# MotorDriver.net
KiCad netlist of a schematic drawn in EAGLE
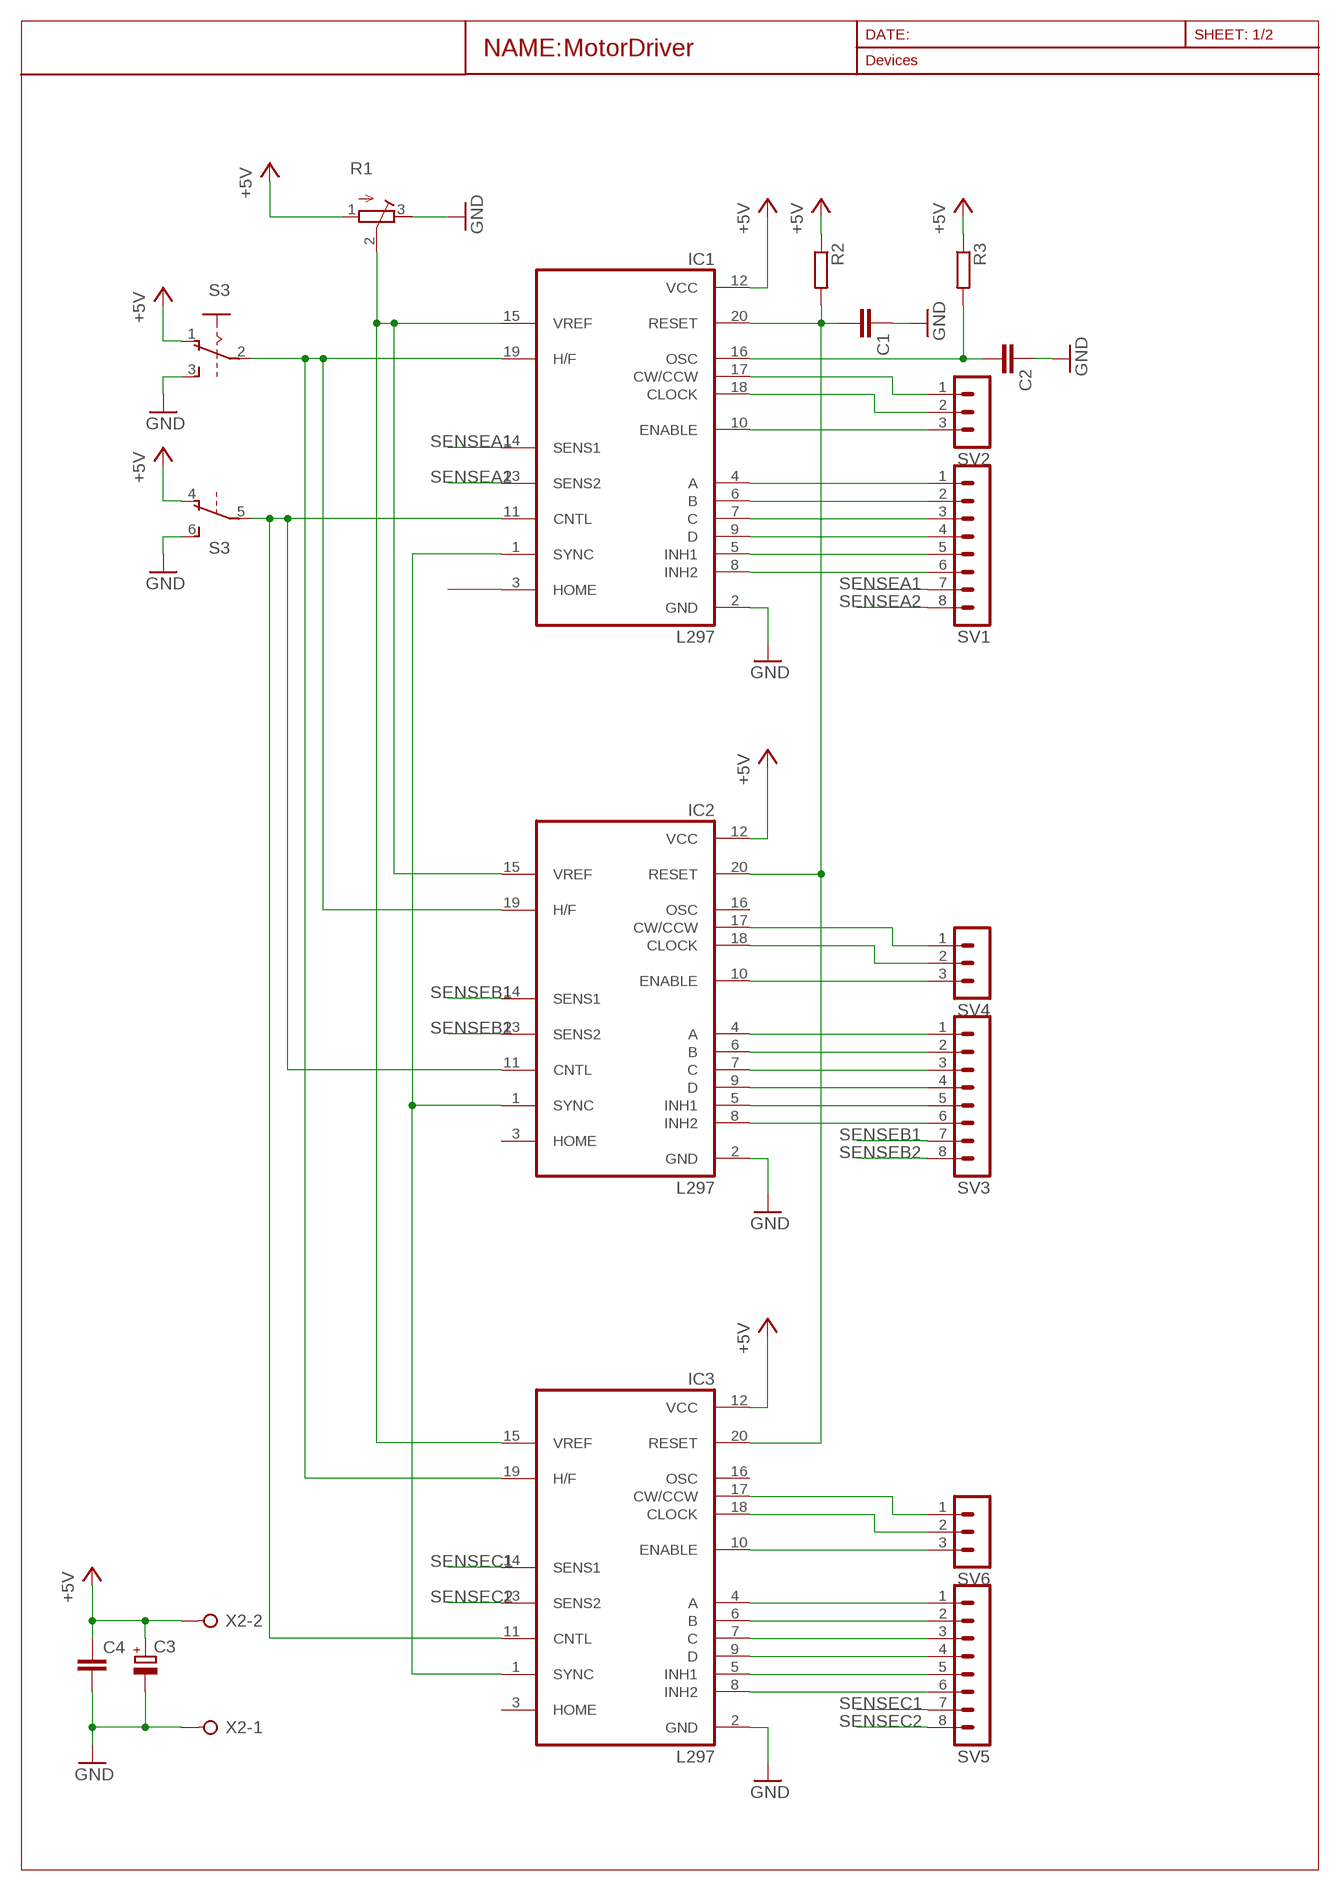
[diagram p0: schematic, sheet 1]

(export (version "E")
  (design (tool "Eeschema 10.0.6"))
  (components
    (comp (ref "C1")
      (value "C-EU050-024X044")
      (footprint "eagle-import:C050-024X044")
      (libsource (lib "eagle-import") (part "C-EU050-024X044"))
    )
    (comp (ref "C2")
      (value "C-EU050-024X044")
      (footprint "eagle-import:C050-024X044")
      (libsource (lib "eagle-import") (part "C-EU050-024X044"))
    )
    (comp (ref "C3")
      (value "CPOL-EUE3.5-8")
      (footprint "eagle-import:E3,5-8")
      (libsource (lib "eagle-import") (part "CPOL-EUE3.5-8"))
    )
    (comp (ref "C4")
      (value "C-EU050-024X044")
      (footprint "eagle-import:C050-024X044")
      (libsource (lib "eagle-import") (part "C-EU050-024X044"))
    )
    (comp (ref "IC1")
      (value "L297")
      (footprint "eagle-import:DIL20")
      (fields (field (name "MPN") "L297/1"))
      (libsource (lib "eagle-import") (part "L297"))
    )
    (comp (ref "IC2")
      (value "L297")
      (footprint "eagle-import:DIL20")
      (fields (field (name "MPN") "L297/1"))
      (libsource (lib "eagle-import") (part "L297"))
    )
    (comp (ref "IC3")
      (value "L297")
      (footprint "eagle-import:DIL20")
      (fields (field (name "MPN") "L297/1"))
      (libsource (lib "eagle-import") (part "L297"))
    )
    (comp (ref "R1")
      (value "R-TRIMM64P")
      (footprint "eagle-import:RTRIM64P")
      (libsource (lib "eagle-import") (part "R-TRIMM64P"))
    )
    (comp (ref "R2")
      (value "R-EU_0207/10")
      (footprint "eagle-import:0207_10")
      (libsource (lib "eagle-import") (part "R-EU_0207/10"))
    )
    (comp (ref "R3")
      (value "R-EU_0207/10")
      (footprint "eagle-import:0207_10")
      (libsource (lib "eagle-import") (part "R-EU_0207/10"))
    )
    (comp (ref "S3")
      (value "A68-A31")
      (footprint "eagle-import:A68-A31")
      (libsource (lib "eagle-import") (part "A68-A31"))
    )
    (comp (ref "SV1")
      (value "MA08-1")
      (footprint "eagle-import:MA08-1")
      (libsource (lib "eagle-import") (part "MA08-1"))
    )
    (comp (ref "SV2")
      (value "MA03-1")
      (footprint "eagle-import:MA03-1")
      (libsource (lib "eagle-import") (part "MA03-1"))
    )
    (comp (ref "SV3")
      (value "MA08-1")
      (footprint "eagle-import:MA08-1")
      (libsource (lib "eagle-import") (part "MA08-1"))
    )
    (comp (ref "SV4")
      (value "MA03-1")
      (footprint "eagle-import:MA03-1")
      (libsource (lib "eagle-import") (part "MA03-1"))
    )
    (comp (ref "SV5")
      (value "MA08-1")
      (footprint "eagle-import:MA08-1")
      (libsource (lib "eagle-import") (part "MA08-1"))
    )
    (comp (ref "SV6")
      (value "MA03-1")
      (footprint "eagle-import:MA03-1")
      (libsource (lib "eagle-import") (part "MA03-1"))
    )
    (comp (ref "X2")
      (value "W237-02P")
      (footprint "eagle-import:W237-132")
      (libsource (lib "eagle-import") (part "W237-02P"))
    )
  )
  (nets
    (net (code "1") (name "+5V") (class "Default")
      (node (ref "C3") (pin "+") (pinfunction "+_+") (pintype "passive"))
      (node (ref "C4") (pin "1") (pinfunction "1_1") (pintype "passive"))
      (node (ref "IC1") (pin "12") (pinfunction "VCC_12") (pintype "power_in"))
      (node (ref "IC2") (pin "12") (pinfunction "VCC_12") (pintype "power_in"))
      (node (ref "IC3") (pin "12") (pinfunction "VCC_12") (pintype "power_in"))
      (node (ref "R1") (pin "1") (pinfunction "A_1") (pintype "passive"))
      (node (ref "R2") (pin "1") (pinfunction "1_1") (pintype "passive"))
      (node (ref "R3") (pin "1") (pinfunction "1_1") (pintype "passive"))
      (node (ref "S3") (pin "1") (pinfunction "O_1") (pintype "passive"))
      (node (ref "S3") (pin "4") (pinfunction "O_4") (pintype "passive"))
      (node (ref "X2") (pin "2") (pinfunction "KL_2") (pintype "passive"))
    )
    (net (code "2") (name "GND") (class "Default")
      (node (ref "C1") (pin "1") (pinfunction "1_1") (pintype "passive"))
      (node (ref "C2") (pin "1") (pinfunction "1_1") (pintype "passive"))
      (node (ref "C3") (pin "-") (pinfunction "-_-") (pintype "passive"))
      (node (ref "C4") (pin "2") (pinfunction "2_2") (pintype "passive"))
      (node (ref "IC1") (pin "2") (pinfunction "GND_2") (pintype "power_in"))
      (node (ref "IC2") (pin "2") (pinfunction "GND_2") (pintype "power_in"))
      (node (ref "IC3") (pin "2") (pinfunction "GND_2") (pintype "power_in"))
      (node (ref "R1") (pin "3") (pinfunction "E_3") (pintype "passive"))
      (node (ref "S3") (pin "3") (pinfunction "S_3") (pintype "passive"))
      (node (ref "S3") (pin "6") (pinfunction "S_6") (pintype "passive"))
      (node (ref "X2") (pin "1") (pinfunction "KL_1") (pintype "passive"))
    )
    (net (code "3") (name "Net-(IC1-A)") (class "Default")
      (node (ref "IC1") (pin "4") (pinfunction "A_4") (pintype "output"))
      (node (ref "SV1") (pin "1") (pinfunction "1_1") (pintype "passive"))
    )
    (net (code "4") (name "Net-(IC1-B)") (class "Default")
      (node (ref "IC1") (pin "6") (pinfunction "B_6") (pintype "output"))
      (node (ref "SV1") (pin "2") (pinfunction "2_2") (pintype "passive"))
    )
    (net (code "5") (name "Net-(IC1-C)") (class "Default")
      (node (ref "IC1") (pin "7") (pinfunction "C_7") (pintype "output"))
      (node (ref "SV1") (pin "3") (pinfunction "3_3") (pintype "passive"))
    )
    (net (code "6") (name "Net-(IC1-CLOCK)") (class "Default")
      (node (ref "IC1") (pin "18") (pinfunction "CLOCK_18") (pintype "input"))
      (node (ref "SV2") (pin "2") (pinfunction "2_2") (pintype "passive"))
    )
    (net (code "7") (name "Net-(IC1-CNTL)") (class "Default")
      (node (ref "IC1") (pin "11") (pinfunction "CNTL_11") (pintype "input"))
      (node (ref "IC2") (pin "11") (pinfunction "CNTL_11") (pintype "input"))
      (node (ref "IC3") (pin "11") (pinfunction "CNTL_11") (pintype "input"))
      (node (ref "S3") (pin "5") (pinfunction "P_5") (pintype "passive"))
    )
    (net (code "8") (name "Net-(IC1-CW{slash}CCW)") (class "Default")
      (node (ref "IC1") (pin "17") (pinfunction "CW/CCW_17") (pintype "input"))
      (node (ref "SV2") (pin "1") (pinfunction "1_1") (pintype "passive"))
    )
    (net (code "9") (name "Net-(IC1-D)") (class "Default")
      (node (ref "IC1") (pin "9") (pinfunction "D_9") (pintype "output"))
      (node (ref "SV1") (pin "4") (pinfunction "4_4") (pintype "passive"))
    )
    (net (code "10") (name "Net-(IC1-ENABLE)") (class "Default")
      (node (ref "IC1") (pin "10") (pinfunction "ENABLE_10") (pintype "input"))
      (node (ref "SV2") (pin "3") (pinfunction "3_3") (pintype "passive"))
    )
    (net (code "11") (name "Net-(IC1-H{slash}F)") (class "Default")
      (node (ref "IC1") (pin "19") (pinfunction "H/F_19") (pintype "input"))
      (node (ref "IC2") (pin "19") (pinfunction "H/F_19") (pintype "input"))
      (node (ref "IC3") (pin "19") (pinfunction "H/F_19") (pintype "input"))
      (node (ref "S3") (pin "2") (pinfunction "P_2") (pintype "passive"))
    )
    (net (code "12") (name "Net-(IC1-INH1)") (class "Default")
      (node (ref "IC1") (pin "5") (pinfunction "INH1_5") (pintype "output"))
      (node (ref "SV1") (pin "5") (pinfunction "5_5") (pintype "passive"))
    )
    (net (code "13") (name "Net-(IC1-INH2)") (class "Default")
      (node (ref "IC1") (pin "8") (pinfunction "INH2_8") (pintype "output"))
      (node (ref "SV1") (pin "6") (pinfunction "6_6") (pintype "passive"))
    )
    (net (code "14") (name "Net-(IC1-OSC)") (class "Default")
      (node (ref "C2") (pin "2") (pinfunction "2_2") (pintype "passive"))
      (node (ref "IC1") (pin "16") (pinfunction "OSC_16") (pintype "bidirectional"))
      (node (ref "R3") (pin "2") (pinfunction "2_2") (pintype "passive"))
    )
    (net (code "15") (name "Net-(IC1-RESET)") (class "Default")
      (node (ref "C1") (pin "2") (pinfunction "2_2") (pintype "passive"))
      (node (ref "IC1") (pin "20") (pinfunction "RESET_20") (pintype "input"))
      (node (ref "IC2") (pin "20") (pinfunction "RESET_20") (pintype "input"))
      (node (ref "IC3") (pin "20") (pinfunction "RESET_20") (pintype "input"))
      (node (ref "R2") (pin "2") (pinfunction "2_2") (pintype "passive"))
    )
    (net (code "16") (name "Net-(IC1-SYNC)") (class "Default")
      (node (ref "IC1") (pin "1") (pinfunction "SYNC_1") (pintype "output"))
      (node (ref "IC2") (pin "1") (pinfunction "SYNC_1") (pintype "output"))
      (node (ref "IC3") (pin "1") (pinfunction "SYNC_1") (pintype "output"))
    )
    (net (code "17") (name "Net-(IC1-VREF)") (class "Default")
      (node (ref "IC1") (pin "15") (pinfunction "VREF_15") (pintype "input"))
      (node (ref "IC2") (pin "15") (pinfunction "VREF_15") (pintype "input"))
      (node (ref "IC3") (pin "15") (pinfunction "VREF_15") (pintype "input"))
      (node (ref "R1") (pin "2") (pinfunction "S_2") (pintype "passive"))
    )
    (net (code "18") (name "Net-(IC2-A)") (class "Default")
      (node (ref "IC2") (pin "4") (pinfunction "A_4") (pintype "output"))
      (node (ref "SV3") (pin "1") (pinfunction "1_1") (pintype "passive"))
    )
    (net (code "19") (name "Net-(IC2-B)") (class "Default")
      (node (ref "IC2") (pin "6") (pinfunction "B_6") (pintype "output"))
      (node (ref "SV3") (pin "2") (pinfunction "2_2") (pintype "passive"))
    )
    (net (code "20") (name "Net-(IC2-C)") (class "Default")
      (node (ref "IC2") (pin "7") (pinfunction "C_7") (pintype "output"))
      (node (ref "SV3") (pin "3") (pinfunction "3_3") (pintype "passive"))
    )
    (net (code "21") (name "Net-(IC2-CLOCK)") (class "Default")
      (node (ref "IC2") (pin "18") (pinfunction "CLOCK_18") (pintype "input"))
      (node (ref "SV4") (pin "2") (pinfunction "2_2") (pintype "passive"))
    )
    (net (code "22") (name "Net-(IC2-CW{slash}CCW)") (class "Default")
      (node (ref "IC2") (pin "17") (pinfunction "CW/CCW_17") (pintype "input"))
      (node (ref "SV4") (pin "1") (pinfunction "1_1") (pintype "passive"))
    )
    (net (code "23") (name "Net-(IC2-D)") (class "Default")
      (node (ref "IC2") (pin "9") (pinfunction "D_9") (pintype "output"))
      (node (ref "SV3") (pin "4") (pinfunction "4_4") (pintype "passive"))
    )
    (net (code "24") (name "Net-(IC2-ENABLE)") (class "Default")
      (node (ref "IC2") (pin "10") (pinfunction "ENABLE_10") (pintype "input"))
      (node (ref "SV4") (pin "3") (pinfunction "3_3") (pintype "passive"))
    )
    (net (code "25") (name "Net-(IC2-INH1)") (class "Default")
      (node (ref "IC2") (pin "5") (pinfunction "INH1_5") (pintype "output"))
      (node (ref "SV3") (pin "5") (pinfunction "5_5") (pintype "passive"))
    )
    (net (code "26") (name "Net-(IC2-INH2)") (class "Default")
      (node (ref "IC2") (pin "8") (pinfunction "INH2_8") (pintype "output"))
      (node (ref "SV3") (pin "6") (pinfunction "6_6") (pintype "passive"))
    )
    (net (code "27") (name "Net-(IC3-A)") (class "Default")
      (node (ref "IC3") (pin "4") (pinfunction "A_4") (pintype "output"))
      (node (ref "SV5") (pin "1") (pinfunction "1_1") (pintype "passive"))
    )
    (net (code "28") (name "Net-(IC3-B)") (class "Default")
      (node (ref "IC3") (pin "6") (pinfunction "B_6") (pintype "output"))
      (node (ref "SV5") (pin "2") (pinfunction "2_2") (pintype "passive"))
    )
    (net (code "29") (name "Net-(IC3-C)") (class "Default")
      (node (ref "IC3") (pin "7") (pinfunction "C_7") (pintype "output"))
      (node (ref "SV5") (pin "3") (pinfunction "3_3") (pintype "passive"))
    )
    (net (code "30") (name "Net-(IC3-CLOCK)") (class "Default")
      (node (ref "IC3") (pin "18") (pinfunction "CLOCK_18") (pintype "input"))
      (node (ref "SV6") (pin "2") (pinfunction "2_2") (pintype "passive"))
    )
    (net (code "31") (name "Net-(IC3-CW{slash}CCW)") (class "Default")
      (node (ref "IC3") (pin "17") (pinfunction "CW/CCW_17") (pintype "input"))
      (node (ref "SV6") (pin "1") (pinfunction "1_1") (pintype "passive"))
    )
    (net (code "32") (name "Net-(IC3-D)") (class "Default")
      (node (ref "IC3") (pin "9") (pinfunction "D_9") (pintype "output"))
      (node (ref "SV5") (pin "4") (pinfunction "4_4") (pintype "passive"))
    )
    (net (code "33") (name "Net-(IC3-ENABLE)") (class "Default")
      (node (ref "IC3") (pin "10") (pinfunction "ENABLE_10") (pintype "input"))
      (node (ref "SV6") (pin "3") (pinfunction "3_3") (pintype "passive"))
    )
    (net (code "34") (name "Net-(IC3-INH1)") (class "Default")
      (node (ref "IC3") (pin "5") (pinfunction "INH1_5") (pintype "output"))
      (node (ref "SV5") (pin "5") (pinfunction "5_5") (pintype "passive"))
    )
    (net (code "35") (name "Net-(IC3-INH2)") (class "Default")
      (node (ref "IC3") (pin "8") (pinfunction "INH2_8") (pintype "output"))
      (node (ref "SV5") (pin "6") (pinfunction "6_6") (pintype "passive"))
    )
    (net (code "36") (name "SENSEA1") (class "Default")
      (node (ref "IC1") (pin "14") (pinfunction "SENS1_14") (pintype "output"))
      (node (ref "SV1") (pin "7") (pinfunction "7_7") (pintype "passive"))
    )
    (net (code "37") (name "SENSEA2") (class "Default")
      (node (ref "IC1") (pin "13") (pinfunction "SENS2_13") (pintype "output"))
      (node (ref "SV1") (pin "8") (pinfunction "8_8") (pintype "passive"))
    )
    (net (code "38") (name "SENSEB1") (class "Default")
      (node (ref "IC2") (pin "14") (pinfunction "SENS1_14") (pintype "output"))
      (node (ref "SV3") (pin "7") (pinfunction "7_7") (pintype "passive"))
    )
    (net (code "39") (name "SENSEB2") (class "Default")
      (node (ref "IC2") (pin "13") (pinfunction "SENS2_13") (pintype "output"))
      (node (ref "SV3") (pin "8") (pinfunction "8_8") (pintype "passive"))
    )
    (net (code "40") (name "SENSEC1") (class "Default")
      (node (ref "IC3") (pin "14") (pinfunction "SENS1_14") (pintype "output"))
      (node (ref "SV5") (pin "7") (pinfunction "7_7") (pintype "passive"))
    )
    (net (code "41") (name "SENSEC2") (class "Default")
      (node (ref "IC3") (pin "13") (pinfunction "SENS2_13") (pintype "output"))
      (node (ref "SV5") (pin "8") (pinfunction "8_8") (pintype "passive"))
    )
    (net (code "42") (name "unconnected-(IC1-HOME-Pad3)") (class "Default")
      (node (ref "IC1") (pin "3") (pinfunction "HOME_3") (pintype "output"))
    )
    (net (code "43") (name "unconnected-(IC2-HOME-Pad3)") (class "Default")
      (node (ref "IC2") (pin "3") (pinfunction "HOME_3") (pintype "output"))
    )
    (net (code "44") (name "unconnected-(IC2-OSC-Pad16)") (class "Default")
      (node (ref "IC2") (pin "16") (pinfunction "OSC_16") (pintype "bidirectional"))
    )
    (net (code "45") (name "unconnected-(IC3-HOME-Pad3)") (class "Default")
      (node (ref "IC3") (pin "3") (pinfunction "HOME_3") (pintype "output"))
    )
    (net (code "46") (name "unconnected-(IC3-OSC-Pad16)") (class "Default")
      (node (ref "IC3") (pin "16") (pinfunction "OSC_16") (pintype "bidirectional"))
    )
  )
)
